# SL_FPGA_Auto_2E.net
KiCad netlist of a schematic drawn in Altium Designer
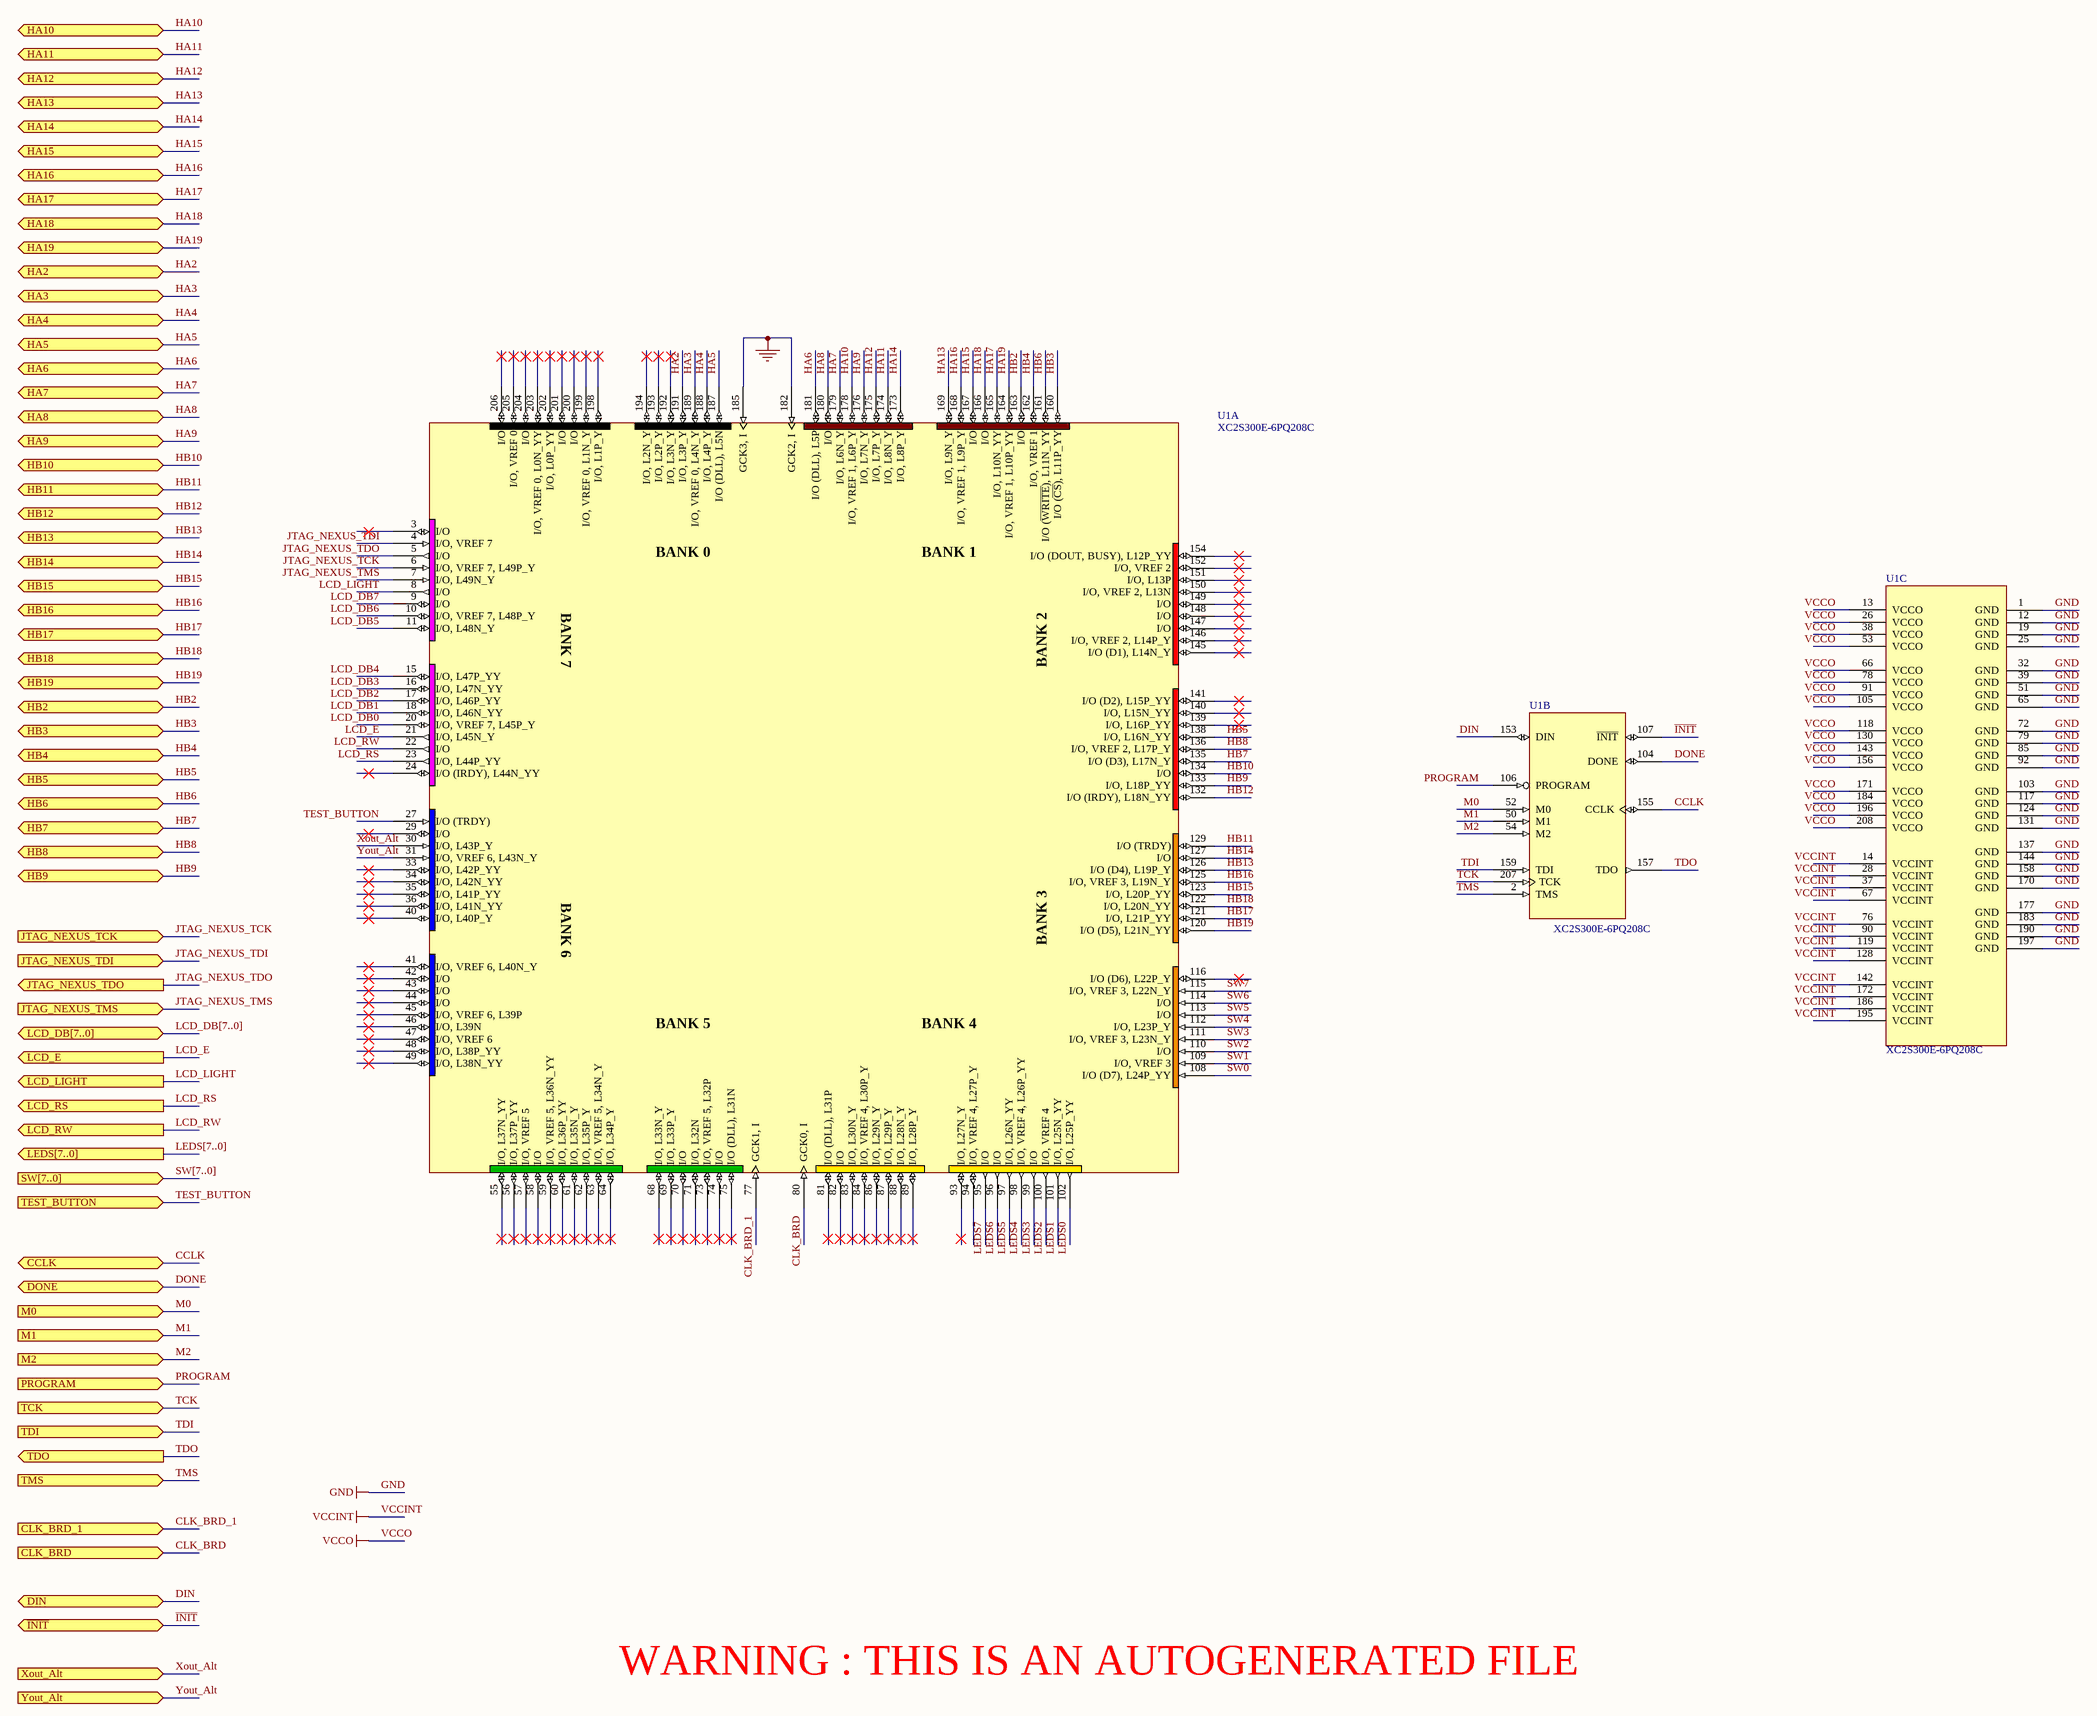
[diagram p0: SL_FPGA_Auto_2E.SchDoc]

(export (version "E")
  (design (tool "Eeschema 10.0.6"))
  (components
    (comp (ref "U1")
      (value "XC2S300E-6PQ208C")
      (footprint "PQ208")
      (description "Spartan-IIE 1.8V FPGA, 208-Pin PQFP, Standard Performance, Commercial Grade")
      (fields (field (name "PUBLISHER") "Altium Limited"))
      (libsource (lib "SpiritLevel_2E") (part "XC2S300E-6PQ208C"))
    )
  )
  (nets
    (net (code "1") (name "/CCLK") (class "Default")
      (node (ref "U1") (pin "155") (pinfunction "CCLK_155") (pintype "bidirectional"))
    )
    (net (code "2") (name "/CLK_BRD") (class "Default")
      (node (ref "U1") (pin "80") (pinfunction "GCK0,_I_80") (pintype "input"))
    )
    (net (code "3") (name "/CLK_BRD_1") (class "Default")
      (node (ref "U1") (pin "77") (pinfunction "GCK1,_I_77") (pintype "input"))
    )
    (net (code "4") (name "/DIN") (class "Default")
      (node (ref "U1") (pin "153") (pinfunction "DIN_153") (pintype "bidirectional"))
    )
    (net (code "5") (name "/DONE") (class "Default")
      (node (ref "U1") (pin "104") (pinfunction "DONE_104") (pintype "bidirectional"))
    )
    (net (code "6") (name "/HA2") (class "Default")
      (node (ref "U1") (pin "191") (pinfunction "I/O,_L3P_Y_191") (pintype "bidirectional"))
    )
    (net (code "7") (name "/HA3") (class "Default")
      (node (ref "U1") (pin "189") (pinfunction "I/O,_VREF_0,_L4N_Y_189") (pintype "bidirectional"))
    )
    (net (code "8") (name "/HA4") (class "Default")
      (node (ref "U1") (pin "188") (pinfunction "I/O,_L4P_Y_188") (pintype "bidirectional"))
    )
    (net (code "9") (name "/HA5") (class "Default")
      (node (ref "U1") (pin "187") (pinfunction "I/O_(DLL),_L5N_187") (pintype "bidirectional"))
    )
    (net (code "10") (name "/HA6") (class "Default")
      (node (ref "U1") (pin "181") (pinfunction "I/O_(DLL),_L5P_181") (pintype "bidirectional"))
    )
    (net (code "11") (name "/HA7") (class "Default")
      (node (ref "U1") (pin "179") (pinfunction "I/O,_L6N_Y_179") (pintype "bidirectional"))
    )
    (net (code "12") (name "/HA8") (class "Default")
      (node (ref "U1") (pin "180") (pinfunction "I/O_180") (pintype "bidirectional"))
    )
    (net (code "13") (name "/HA9") (class "Default")
      (node (ref "U1") (pin "176") (pinfunction "I/O,_L7N_Y_176") (pintype "bidirectional"))
    )
    (net (code "14") (name "/HA10") (class "Default")
      (node (ref "U1") (pin "178") (pinfunction "I/O,_VREF_1,_L6P_Y_178") (pintype "bidirectional"))
    )
    (net (code "15") (name "/HA11") (class "Default")
      (node (ref "U1") (pin "174") (pinfunction "I/O,_L8N_Y_174") (pintype "bidirectional"))
    )
    (net (code "16") (name "/HA12") (class "Default")
      (node (ref "U1") (pin "175") (pinfunction "I/O,_L7P_Y_175") (pintype "bidirectional"))
    )
    (net (code "17") (name "/HA13") (class "Default")
      (node (ref "U1") (pin "169") (pinfunction "I/O,_L9N_Y_169") (pintype "bidirectional"))
    )
    (net (code "18") (name "/HA14") (class "Default")
      (node (ref "U1") (pin "173") (pinfunction "I/O,_L8P_Y_173") (pintype "bidirectional"))
    )
    (net (code "19") (name "/HA15") (class "Default")
      (node (ref "U1") (pin "167") (pinfunction "I/O_167") (pintype "bidirectional"))
    )
    (net (code "20") (name "/HA16") (class "Default")
      (node (ref "U1") (pin "168") (pinfunction "I/O,_VREF_1,_L9P_Y_168") (pintype "bidirectional"))
    )
    (net (code "21") (name "/HA17") (class "Default")
      (node (ref "U1") (pin "165") (pinfunction "I/O,_L10N_YY_165") (pintype "bidirectional"))
    )
    (net (code "22") (name "/HA18") (class "Default")
      (node (ref "U1") (pin "166") (pinfunction "I/O_166") (pintype "bidirectional"))
    )
    (net (code "23") (name "/HA19") (class "Default")
      (node (ref "U1") (pin "164") (pinfunction "I/O,_VREF_1,_L10P_YY_164") (pintype "bidirectional"))
    )
    (net (code "24") (name "/HB2") (class "Default")
      (node (ref "U1") (pin "163") (pinfunction "I/O_163") (pintype "bidirectional"))
    )
    (net (code "25") (name "/HB3") (class "Default")
      (node (ref "U1") (pin "160") (pinfunction "I/O_(~{CS}),_L11P_YY_160") (pintype "bidirectional"))
    )
    (net (code "26") (name "/HB4") (class "Default")
      (node (ref "U1") (pin "162") (pinfunction "I/O,_VREF_1_162") (pintype "bidirectional"))
    )
    (net (code "27") (name "/HB5") (class "Default")
      (node (ref "U1") (pin "138") (pinfunction "I/O,_L16N_YY_138") (pintype "bidirectional"))
    )
    (net (code "28") (name "/HB6") (class "Default")
      (node (ref "U1") (pin "161") (pinfunction "I/O_(~{WRITE}),_L11N_YY_161") (pintype "bidirectional"))
    )
    (net (code "29") (name "/HB7") (class "Default")
      (node (ref "U1") (pin "135") (pinfunction "I/O_(D3),_L17N_Y_135") (pintype "bidirectional"))
    )
    (net (code "30") (name "/HB8") (class "Default")
      (node (ref "U1") (pin "136") (pinfunction "I/O,_VREF_2,_L17P_Y_136") (pintype "bidirectional"))
    )
    (net (code "31") (name "/HB9") (class "Default")
      (node (ref "U1") (pin "133") (pinfunction "I/O,_L18P_YY_133") (pintype "bidirectional"))
    )
    (net (code "32") (name "/HB10") (class "Default")
      (node (ref "U1") (pin "134") (pinfunction "I/O_134") (pintype "bidirectional"))
    )
    (net (code "33") (name "/HB11") (class "Default")
      (node (ref "U1") (pin "129") (pinfunction "I/O_(TRDY)_129") (pintype "bidirectional"))
    )
    (net (code "34") (name "/HB12") (class "Default")
      (node (ref "U1") (pin "132") (pinfunction "I/O_(IRDY),_L18N_YY_132") (pintype "bidirectional"))
    )
    (net (code "35") (name "/HB13") (class "Default")
      (node (ref "U1") (pin "126") (pinfunction "I/O_(D4),_L19P_Y_126") (pintype "bidirectional"))
    )
    (net (code "36") (name "/HB14") (class "Default")
      (node (ref "U1") (pin "127") (pinfunction "I/O_127") (pintype "bidirectional"))
    )
    (net (code "37") (name "/HB15") (class "Default")
      (node (ref "U1") (pin "123") (pinfunction "I/O,_L20P_YY_123") (pintype "bidirectional"))
    )
    (net (code "38") (name "/HB16") (class "Default")
      (node (ref "U1") (pin "125") (pinfunction "I/O,_VREF_3,_L19N_Y_125") (pintype "bidirectional"))
    )
    (net (code "39") (name "/HB17") (class "Default")
      (node (ref "U1") (pin "121") (pinfunction "I/O,_L21P_YY_121") (pintype "bidirectional"))
    )
    (net (code "40") (name "/HB18") (class "Default")
      (node (ref "U1") (pin "122") (pinfunction "I/O,_L20N_YY_122") (pintype "bidirectional"))
    )
    (net (code "41") (name "/HB19") (class "Default")
      (node (ref "U1") (pin "120") (pinfunction "I/O_(D5),_L21N_YY_120") (pintype "bidirectional"))
    )
    (net (code "42") (name "/JTAG_NEXUS_TCK") (class "Default")
      (node (ref "U1") (pin "6") (pinfunction "I/O,_VREF_7,_L49P_Y_6") (pintype "input"))
    )
    (net (code "43") (name "/JTAG_NEXUS_TDI") (class "Default")
      (node (ref "U1") (pin "4") (pinfunction "I/O,_VREF_7_4") (pintype "input"))
    )
    (net (code "44") (name "/JTAG_NEXUS_TDO") (class "Default")
      (node (ref "U1") (pin "5") (pinfunction "I/O_5") (pintype "output"))
    )
    (net (code "45") (name "/JTAG_NEXUS_TMS") (class "Default")
      (node (ref "U1") (pin "7") (pinfunction "I/O,_L49N_Y_7") (pintype "input"))
    )
    (net (code "46") (name "/LCD_DB0") (class "Default")
      (node (ref "U1") (pin "20") (pinfunction "I/O,_VREF_7,_L45P_Y_20") (pintype "bidirectional"))
    )
    (net (code "47") (name "/LCD_DB1") (class "Default")
      (node (ref "U1") (pin "18") (pinfunction "I/O,_L46N_YY_18") (pintype "bidirectional"))
    )
    (net (code "48") (name "/LCD_DB2") (class "Default")
      (node (ref "U1") (pin "17") (pinfunction "I/O,_L46P_YY_17") (pintype "bidirectional"))
    )
    (net (code "49") (name "/LCD_DB3") (class "Default")
      (node (ref "U1") (pin "16") (pinfunction "I/O,_L47N_YY_16") (pintype "bidirectional"))
    )
    (net (code "50") (name "/LCD_DB4") (class "Default")
      (node (ref "U1") (pin "15") (pinfunction "I/O,_L47P_YY_15") (pintype "bidirectional"))
    )
    (net (code "51") (name "/LCD_DB5") (class "Default")
      (node (ref "U1") (pin "11") (pinfunction "I/O,_L48N_Y_11") (pintype "bidirectional"))
    )
    (net (code "52") (name "/LCD_DB6") (class "Default")
      (node (ref "U1") (pin "10") (pinfunction "I/O,_VREF_7,_L48P_Y_10") (pintype "bidirectional"))
    )
    (net (code "53") (name "/LCD_DB7") (class "Default")
      (node (ref "U1") (pin "9") (pinfunction "I/O_9") (pintype "bidirectional"))
    )
    (net (code "55") (name "/LCD_E") (class "Default")
      (node (ref "U1") (pin "21") (pinfunction "I/O,_L45N_Y_21") (pintype "output"))
    )
    (net (code "56") (name "/LCD_LIGHT") (class "Default")
      (node (ref "U1") (pin "8") (pinfunction "I/O_8") (pintype "output"))
    )
    (net (code "57") (name "/LCD_RS") (class "Default")
      (node (ref "U1") (pin "23") (pinfunction "I/O,_L44P_YY_23") (pintype "output"))
    )
    (net (code "58") (name "/LCD_RW") (class "Default")
      (node (ref "U1") (pin "22") (pinfunction "I/O_22") (pintype "output"))
    )
    (net (code "59") (name "/LEDS0") (class "Default")
      (node (ref "U1") (pin "102") (pinfunction "I/O,_L25P_YY_102") (pintype "output"))
    )
    (net (code "60") (name "/LEDS1") (class "Default")
      (node (ref "U1") (pin "101") (pinfunction "I/O,_L25N_YY_101") (pintype "output"))
    )
    (net (code "61") (name "/LEDS2") (class "Default")
      (node (ref "U1") (pin "100") (pinfunction "I/O,_VREF_4_100") (pintype "output"))
    )
    (net (code "62") (name "/LEDS3") (class "Default")
      (node (ref "U1") (pin "99") (pinfunction "I/O_99") (pintype "output"))
    )
    (net (code "63") (name "/LEDS4") (class "Default")
      (node (ref "U1") (pin "98") (pinfunction "I/O,_VREF_4,_L26P_YY_98") (pintype "output"))
    )
    (net (code "64") (name "/LEDS5") (class "Default")
      (node (ref "U1") (pin "97") (pinfunction "I/O,_L26N_YY_97") (pintype "output"))
    )
    (net (code "65") (name "/LEDS6") (class "Default")
      (node (ref "U1") (pin "96") (pinfunction "I/O_96") (pintype "output"))
    )
    (net (code "66") (name "/LEDS7") (class "Default")
      (node (ref "U1") (pin "95") (pinfunction "I/O_95") (pintype "output"))
    )
    (net (code "68") (name "/M0") (class "Default")
      (node (ref "U1") (pin "52") (pinfunction "M0_52") (pintype "input"))
    )
    (net (code "69") (name "/M1") (class "Default")
      (node (ref "U1") (pin "50") (pinfunction "M1_50") (pintype "input"))
    )
    (net (code "70") (name "/M2") (class "Default")
      (node (ref "U1") (pin "54") (pinfunction "M2_54") (pintype "input"))
    )
    (net (code "71") (name "/PROGRAM") (class "Default")
      (node (ref "U1") (pin "106") (pinfunction "PROGRAM_106") (pintype "input"))
    )
    (net (code "72") (name "/SW0") (class "Default")
      (node (ref "U1") (pin "108") (pinfunction "I/O_(D7),_L24P_YY_108") (pintype "input"))
    )
    (net (code "73") (name "/SW1") (class "Default")
      (node (ref "U1") (pin "109") (pinfunction "I/O,_VREF_3_109") (pintype "input"))
    )
    (net (code "74") (name "/SW2") (class "Default")
      (node (ref "U1") (pin "110") (pinfunction "I/O_110") (pintype "input"))
    )
    (net (code "75") (name "/SW3") (class "Default")
      (node (ref "U1") (pin "111") (pinfunction "I/O,_VREF_3,_L23N_Y_111") (pintype "input"))
    )
    (net (code "76") (name "/SW4") (class "Default")
      (node (ref "U1") (pin "112") (pinfunction "I/O,_L23P_Y_112") (pintype "input"))
    )
    (net (code "77") (name "/SW5") (class "Default")
      (node (ref "U1") (pin "113") (pinfunction "I/O_113") (pintype "input"))
    )
    (net (code "78") (name "/SW6") (class "Default")
      (node (ref "U1") (pin "114") (pinfunction "I/O_114") (pintype "input"))
    )
    (net (code "79") (name "/SW7") (class "Default")
      (node (ref "U1") (pin "115") (pinfunction "I/O,_VREF_3,_L22N_Y_115") (pintype "input"))
    )
    (net (code "81") (name "/TCK") (class "Default")
      (node (ref "U1") (pin "207") (pinfunction "TCK_207") (pintype "input"))
    )
    (net (code "82") (name "/TDI") (class "Default")
      (node (ref "U1") (pin "159") (pinfunction "TDI_159") (pintype "input"))
    )
    (net (code "83") (name "/TDO") (class "Default")
      (node (ref "U1") (pin "157") (pinfunction "TDO_157") (pintype "output"))
    )
    (net (code "84") (name "/TEST_BUTTON") (class "Default")
      (node (ref "U1") (pin "27") (pinfunction "I/O_(TRDY)_27") (pintype "input"))
    )
    (net (code "85") (name "/TMS") (class "Default")
      (node (ref "U1") (pin "2") (pinfunction "TMS_2") (pintype "input"))
    )
    (net (code "86") (name "/Xout_Alt") (class "Default")
      (node (ref "U1") (pin "30") (pinfunction "I/O,_L43P_Y_30") (pintype "input"))
    )
    (net (code "87") (name "/Yout_Alt") (class "Default")
      (node (ref "U1") (pin "31") (pinfunction "I/O,_VREF_6,_L43N_Y_31") (pintype "input"))
    )
    (net (code "88") (name "/~{INIT}") (class "Default")
      (node (ref "U1") (pin "107") (pinfunction "~{INIT}_107") (pintype "bidirectional"))
    )
    (net (code "89") (name "GND") (class "Default")
      (node (ref "U1") (pin "1") (pinfunction "GND_1") (pintype "power_in"))
      (node (ref "U1") (pin "103") (pinfunction "GND_103") (pintype "power_in"))
      (node (ref "U1") (pin "117") (pinfunction "GND_117") (pintype "power_in"))
      (node (ref "U1") (pin "12") (pinfunction "GND_12") (pintype "power_in"))
      (node (ref "U1") (pin "124") (pinfunction "GND_124") (pintype "power_in"))
      (node (ref "U1") (pin "131") (pinfunction "GND_131") (pintype "power_in"))
      (node (ref "U1") (pin "137") (pinfunction "GND_137") (pintype "power_in"))
      (node (ref "U1") (pin "144") (pinfunction "GND_144") (pintype "power_in"))
      (node (ref "U1") (pin "158") (pinfunction "GND_158") (pintype "power_in"))
      (node (ref "U1") (pin "170") (pinfunction "GND_170") (pintype "power_in"))
      (node (ref "U1") (pin "177") (pinfunction "GND_177") (pintype "power_in"))
      (node (ref "U1") (pin "182") (pinfunction "GCK2,_I_182") (pintype "input"))
      (node (ref "U1") (pin "183") (pinfunction "GND_183") (pintype "power_in"))
      (node (ref "U1") (pin "185") (pinfunction "GCK3,_I_185") (pintype "input"))
      (node (ref "U1") (pin "19") (pinfunction "GND_19") (pintype "power_in"))
      (node (ref "U1") (pin "190") (pinfunction "GND_190") (pintype "power_in"))
      (node (ref "U1") (pin "197") (pinfunction "GND_197") (pintype "power_in"))
      (node (ref "U1") (pin "25") (pinfunction "GND_25") (pintype "power_in"))
      (node (ref "U1") (pin "32") (pinfunction "GND_32") (pintype "power_in"))
      (node (ref "U1") (pin "39") (pinfunction "GND_39") (pintype "power_in"))
      (node (ref "U1") (pin "51") (pinfunction "GND_51") (pintype "power_in"))
      (node (ref "U1") (pin "65") (pinfunction "GND_65") (pintype "power_in"))
      (node (ref "U1") (pin "72") (pinfunction "GND_72") (pintype "power_in"))
      (node (ref "U1") (pin "79") (pinfunction "GND_79") (pintype "power_in"))
      (node (ref "U1") (pin "85") (pinfunction "GND_85") (pintype "power_in"))
      (node (ref "U1") (pin "92") (pinfunction "GND_92") (pintype "power_in"))
    )
    (net (code "90") (name "VCCINT") (class "Default")
      (node (ref "U1") (pin "119") (pinfunction "VCCINT_119") (pintype "power_in"))
      (node (ref "U1") (pin "128") (pinfunction "VCCINT_128") (pintype "power_in"))
      (node (ref "U1") (pin "14") (pinfunction "VCCINT_14") (pintype "power_in"))
      (node (ref "U1") (pin "142") (pinfunction "VCCINT_142") (pintype "power_in"))
      (node (ref "U1") (pin "172") (pinfunction "VCCINT_172") (pintype "power_in"))
      (node (ref "U1") (pin "186") (pinfunction "VCCINT_186") (pintype "power_in"))
      (node (ref "U1") (pin "195") (pinfunction "VCCINT_195") (pintype "power_in"))
      (node (ref "U1") (pin "28") (pinfunction "VCCINT_28") (pintype "power_in"))
      (node (ref "U1") (pin "37") (pinfunction "VCCINT_37") (pintype "power_in"))
      (node (ref "U1") (pin "67") (pinfunction "VCCINT_67") (pintype "power_in"))
      (node (ref "U1") (pin "76") (pinfunction "VCCINT_76") (pintype "power_in"))
      (node (ref "U1") (pin "90") (pinfunction "VCCINT_90") (pintype "power_in"))
    )
    (net (code "91") (name "VCCO") (class "Default")
      (node (ref "U1") (pin "105") (pinfunction "VCCO_105") (pintype "power_in"))
      (node (ref "U1") (pin "118") (pinfunction "VCCO_118") (pintype "power_in"))
      (node (ref "U1") (pin "13") (pinfunction "VCCO_13") (pintype "power_in"))
      (node (ref "U1") (pin "130") (pinfunction "VCCO_130") (pintype "power_in"))
      (node (ref "U1") (pin "143") (pinfunction "VCCO_143") (pintype "power_in"))
      (node (ref "U1") (pin "156") (pinfunction "VCCO_156") (pintype "power_in"))
      (node (ref "U1") (pin "171") (pinfunction "VCCO_171") (pintype "power_in"))
      (node (ref "U1") (pin "184") (pinfunction "VCCO_184") (pintype "power_in"))
      (node (ref "U1") (pin "196") (pinfunction "VCCO_196") (pintype "power_in"))
      (node (ref "U1") (pin "208") (pinfunction "VCCO_208") (pintype "power_in"))
      (node (ref "U1") (pin "26") (pinfunction "VCCO_26") (pintype "power_in"))
      (node (ref "U1") (pin "38") (pinfunction "VCCO_38") (pintype "power_in"))
      (node (ref "U1") (pin "53") (pinfunction "VCCO_53") (pintype "power_in"))
      (node (ref "U1") (pin "66") (pinfunction "VCCO_66") (pintype "power_in"))
      (node (ref "U1") (pin "78") (pinfunction "VCCO_78") (pintype "power_in"))
      (node (ref "U1") (pin "91") (pinfunction "VCCO_91") (pintype "power_in"))
    )
    (net (code "92") (name "unconnected-(U1A-I{slash}O,_L0P_YY-Pad202)") (class "Default")
      (node (ref "U1") (pin "202") (pinfunction "I/O,_L0P_YY_202") (pintype "bidirectional"))
    )
    (net (code "93") (name "unconnected-(U1A-I{slash}O,_L1P_Y-Pad198)") (class "Default")
      (node (ref "U1") (pin "198") (pinfunction "I/O,_L1P_Y_198") (pintype "bidirectional"))
    )
    (net (code "94") (name "unconnected-(U1A-I{slash}O,_L2N_Y-Pad194)") (class "Default")
      (node (ref "U1") (pin "194") (pinfunction "I/O,_L2N_Y_194") (pintype "bidirectional"))
    )
    (net (code "95") (name "unconnected-(U1A-I{slash}O,_L2P_Y-Pad193)") (class "Default")
      (node (ref "U1") (pin "193") (pinfunction "I/O,_L2P_Y_193") (pintype "bidirectional"))
    )
    (net (code "96") (name "unconnected-(U1A-I{slash}O,_L3N_Y-Pad192)") (class "Default")
      (node (ref "U1") (pin "192") (pinfunction "I/O,_L3N_Y_192") (pintype "bidirectional"))
    )
    (net (code "97") (name "unconnected-(U1A-I{slash}O,_L13P-Pad151)") (class "Default")
      (node (ref "U1") (pin "151") (pinfunction "I/O,_L13P_151") (pintype "bidirectional"))
    )
    (net (code "98") (name "unconnected-(U1A-I{slash}O,_L15N_YY-Pad140)") (class "Default")
      (node (ref "U1") (pin "140") (pinfunction "I/O,_L15N_YY_140") (pintype "bidirectional"))
    )
    (net (code "99") (name "unconnected-(U1A-I{slash}O,_L16P_YY-Pad139)") (class "Default")
      (node (ref "U1") (pin "139") (pinfunction "I/O,_L16P_YY_139") (pintype "bidirectional"))
    )
    (net (code "100") (name "unconnected-(U1A-I{slash}O,_L27N_Y-Pad93)") (class "Default")
      (node (ref "U1") (pin "93") (pinfunction "I/O,_L27N_Y_93") (pintype "bidirectional"))
    )
    (net (code "101") (name "unconnected-(U1A-I{slash}O,_L28N_Y-Pad88)") (class "Default")
      (node (ref "U1") (pin "88") (pinfunction "I/O,_L28N_Y_88") (pintype "bidirectional"))
    )
    (net (code "102") (name "unconnected-(U1A-I{slash}O,_L28P_Y-Pad89)") (class "Default")
      (node (ref "U1") (pin "89") (pinfunction "I/O,_L28P_Y_89") (pintype "bidirectional"))
    )
    (net (code "103") (name "unconnected-(U1A-I{slash}O,_L29N_Y-Pad86)") (class "Default")
      (node (ref "U1") (pin "86") (pinfunction "I/O,_L29N_Y_86") (pintype "bidirectional"))
    )
    (net (code "104") (name "unconnected-(U1A-I{slash}O,_L29P_Y-Pad87)") (class "Default")
      (node (ref "U1") (pin "87") (pinfunction "I/O,_L29P_Y_87") (pintype "bidirectional"))
    )
    (net (code "105") (name "unconnected-(U1A-I{slash}O,_L30N_Y-Pad83)") (class "Default")
      (node (ref "U1") (pin "83") (pinfunction "I/O,_L30N_Y_83") (pintype "bidirectional"))
    )
    (net (code "106") (name "unconnected-(U1A-I{slash}O,_L32N-Pad71)") (class "Default")
      (node (ref "U1") (pin "71") (pinfunction "I/O,_L32N_71") (pintype "bidirectional"))
    )
    (net (code "107") (name "unconnected-(U1A-I{slash}O,_L33N_Y-Pad68)") (class "Default")
      (node (ref "U1") (pin "68") (pinfunction "I/O,_L33N_Y_68") (pintype "bidirectional"))
    )
    (net (code "108") (name "unconnected-(U1A-I{slash}O,_L33P_Y-Pad69)") (class "Default")
      (node (ref "U1") (pin "69") (pinfunction "I/O,_L33P_Y_69") (pintype "bidirectional"))
    )
    (net (code "109") (name "unconnected-(U1A-I{slash}O,_L34P_Y-Pad64)") (class "Default")
      (node (ref "U1") (pin "64") (pinfunction "I/O,_L34P_Y_64") (pintype "bidirectional"))
    )
    (net (code "110") (name "unconnected-(U1A-I{slash}O,_L35N_Y-Pad61)") (class "Default")
      (node (ref "U1") (pin "61") (pinfunction "I/O,_L35N_Y_61") (pintype "bidirectional"))
    )
    (net (code "111") (name "unconnected-(U1A-I{slash}O,_L35P_Y-Pad62)") (class "Default")
      (node (ref "U1") (pin "62") (pinfunction "I/O,_L35P_Y_62") (pintype "bidirectional"))
    )
    (net (code "112") (name "unconnected-(U1A-I{slash}O,_L36P_YY-Pad60)") (class "Default")
      (node (ref "U1") (pin "60") (pinfunction "I/O,_L36P_YY_60") (pintype "bidirectional"))
    )
    (net (code "113") (name "unconnected-(U1A-I{slash}O,_L37N_YY-Pad55)") (class "Default")
      (node (ref "U1") (pin "55") (pinfunction "I/O,_L37N_YY_55") (pintype "bidirectional"))
    )
    (net (code "114") (name "unconnected-(U1A-I{slash}O,_L37P_YY-Pad56)") (class "Default")
      (node (ref "U1") (pin "56") (pinfunction "I/O,_L37P_YY_56") (pintype "bidirectional"))
    )
    (net (code "115") (name "unconnected-(U1A-I{slash}O,_L38N_YY-Pad49)") (class "Default")
      (node (ref "U1") (pin "49") (pinfunction "I/O,_L38N_YY_49") (pintype "bidirectional"))
    )
    (net (code "116") (name "unconnected-(U1A-I{slash}O,_L38P_YY-Pad48)") (class "Default")
      (node (ref "U1") (pin "48") (pinfunction "I/O,_L38P_YY_48") (pintype "bidirectional"))
    )
    (net (code "117") (name "unconnected-(U1A-I{slash}O,_L39N-Pad46)") (class "Default")
      (node (ref "U1") (pin "46") (pinfunction "I/O,_L39N_46") (pintype "bidirectional"))
    )
    (net (code "118") (name "unconnected-(U1A-I{slash}O,_L40P_Y-Pad40)") (class "Default")
      (node (ref "U1") (pin "40") (pinfunction "I/O,_L40P_Y_40") (pintype "bidirectional"))
    )
    (net (code "119") (name "unconnected-(U1A-I{slash}O,_L41N_YY-Pad36)") (class "Default")
      (node (ref "U1") (pin "36") (pinfunction "I/O,_L41N_YY_36") (pintype "bidirectional"))
    )
    (net (code "120") (name "unconnected-(U1A-I{slash}O,_L41P_YY-Pad35)") (class "Default")
      (node (ref "U1") (pin "35") (pinfunction "I/O,_L41P_YY_35") (pintype "bidirectional"))
    )
    (net (code "121") (name "unconnected-(U1A-I{slash}O,_L42N_YY-Pad34)") (class "Default")
      (node (ref "U1") (pin "34") (pinfunction "I/O,_L42N_YY_34") (pintype "bidirectional"))
    )
    (net (code "122") (name "unconnected-(U1A-I{slash}O,_L42P_YY-Pad33)") (class "Default")
      (node (ref "U1") (pin "33") (pinfunction "I/O,_L42P_YY_33") (pintype "bidirectional"))
    )
    (net (code "123") (name "unconnected-(U1A-I{slash}O,_VREF_0,_L0N_YY-Pad203)") (class "Default")
      (node (ref "U1") (pin "203") (pinfunction "I/O,_VREF_0,_L0N_YY_203") (pintype "bidirectional"))
    )
    (net (code "124") (name "unconnected-(U1A-I{slash}O,_VREF_0,_L1N_Y-Pad199)") (class "Default")
      (node (ref "U1") (pin "199") (pinfunction "I/O,_VREF_0,_L1N_Y_199") (pintype "bidirectional"))
    )
    (net (code "125") (name "unconnected-(U1A-I{slash}O,_VREF_0-Pad205)") (class "Default")
      (node (ref "U1") (pin "205") (pinfunction "I/O,_VREF_0_205") (pintype "bidirectional"))
    )
    (net (code "126") (name "unconnected-(U1A-I{slash}O,_VREF_2,_L13N-Pad150)") (class "Default")
      (node (ref "U1") (pin "150") (pinfunction "I/O,_VREF_2,_L13N_150") (pintype "bidirectional"))
    )
    (net (code "127") (name "unconnected-(U1A-I{slash}O,_VREF_2,_L14P_Y-Pad146)") (class "Default")
      (node (ref "U1") (pin "146") (pinfunction "I/O,_VREF_2,_L14P_Y_146") (pintype "bidirectional"))
    )
    (net (code "128") (name "unconnected-(U1A-I{slash}O,_VREF_2-Pad152)") (class "Default")
      (node (ref "U1") (pin "152") (pinfunction "I/O,_VREF_2_152") (pintype "bidirectional"))
    )
    (net (code "129") (name "unconnected-(U1A-I{slash}O,_VREF_4,_L27P_Y-Pad94)") (class "Default")
      (node (ref "U1") (pin "94") (pinfunction "I/O,_VREF_4,_L27P_Y_94") (pintype "bidirectional"))
    )
    (net (code "130") (name "unconnected-(U1A-I{slash}O,_VREF_4,_L30P_Y-Pad84)") (class "Default")
      (node (ref "U1") (pin "84") (pinfunction "I/O,_VREF_4,_L30P_Y_84") (pintype "bidirectional"))
    )
    (net (code "131") (name "unconnected-(U1A-I{slash}O,_VREF_5,_L32P-Pad73)") (class "Default")
      (node (ref "U1") (pin "73") (pinfunction "I/O,_VREF_5,_L32P_73") (pintype "bidirectional"))
    )
    (net (code "132") (name "unconnected-(U1A-I{slash}O,_VREF_5,_L34N_Y-Pad63)") (class "Default")
      (node (ref "U1") (pin "63") (pinfunction "I/O,_VREF_5,_L34N_Y_63") (pintype "bidirectional"))
    )
    (net (code "133") (name "unconnected-(U1A-I{slash}O,_VREF_5,_L36N_YY-Pad59)") (class "Default")
      (node (ref "U1") (pin "59") (pinfunction "I/O,_VREF_5,_L36N_YY_59") (pintype "bidirectional"))
    )
    (net (code "134") (name "unconnected-(U1A-I{slash}O,_VREF_5-Pad57)") (class "Default")
      (node (ref "U1") (pin "57") (pinfunction "I/O,_VREF_5_57") (pintype "bidirectional"))
    )
    (net (code "135") (name "unconnected-(U1A-I{slash}O,_VREF_6,_L39P-Pad45)") (class "Default")
      (node (ref "U1") (pin "45") (pinfunction "I/O,_VREF_6,_L39P_45") (pintype "bidirectional"))
    )
    (net (code "136") (name "unconnected-(U1A-I{slash}O,_VREF_6,_L40N_Y-Pad41)") (class "Default")
      (node (ref "U1") (pin "41") (pinfunction "I/O,_VREF_6,_L40N_Y_41") (pintype "bidirectional"))
    )
    (net (code "137") (name "unconnected-(U1A-I{slash}O,_VREF_6-Pad47)") (class "Default")
      (node (ref "U1") (pin "47") (pinfunction "I/O,_VREF_6_47") (pintype "bidirectional"))
    )
    (net (code "138") (name "unconnected-(U1A-I{slash}O-Pad3)") (class "Default")
      (node (ref "U1") (pin "3") (pinfunction "I/O_3") (pintype "bidirectional"))
    )
    (net (code "139") (name "unconnected-(U1A-I{slash}O-Pad29)") (class "Default")
      (node (ref "U1") (pin "29") (pinfunction "I/O_29") (pintype "bidirectional"))
    )
    (net (code "140") (name "unconnected-(U1A-I{slash}O-Pad42)") (class "Default")
      (node (ref "U1") (pin "42") (pinfunction "I/O_42") (pintype "bidirectional"))
    )
    (net (code "141") (name "unconnected-(U1A-I{slash}O-Pad43)") (class "Default")
      (node (ref "U1") (pin "43") (pinfunction "I/O_43") (pintype "bidirectional"))
    )
    (net (code "142") (name "unconnected-(U1A-I{slash}O-Pad44)") (class "Default")
      (node (ref "U1") (pin "44") (pinfunction "I/O_44") (pintype "bidirectional"))
    )
    (net (code "143") (name "unconnected-(U1A-I{slash}O-Pad58)") (class "Default")
      (node (ref "U1") (pin "58") (pinfunction "I/O_58") (pintype "bidirectional"))
    )
    (net (code "144") (name "unconnected-(U1A-I{slash}O-Pad70)") (class "Default")
      (node (ref "U1") (pin "70") (pinfunction "I/O_70") (pintype "bidirectional"))
    )
    (net (code "145") (name "unconnected-(U1A-I{slash}O-Pad74)") (class "Default")
      (node (ref "U1") (pin "74") (pinfunction "I/O_74") (pintype "bidirectional"))
    )
    (net (code "146") (name "unconnected-(U1A-I{slash}O-Pad82)") (class "Default")
      (node (ref "U1") (pin "82") (pinfunction "I/O_82") (pintype "bidirectional"))
    )
    (net (code "147") (name "unconnected-(U1A-I{slash}O-Pad147)") (class "Default")
      (node (ref "U1") (pin "147") (pinfunction "I/O_147") (pintype "bidirectional"))
    )
    (net (code "148") (name "unconnected-(U1A-I{slash}O-Pad148)") (class "Default")
      (node (ref "U1") (pin "148") (pinfunction "I/O_148") (pintype "bidirectional"))
    )
    (net (code "149") (name "unconnected-(U1A-I{slash}O-Pad149)") (class "Default")
      (node (ref "U1") (pin "149") (pinfunction "I/O_149") (pintype "bidirectional"))
    )
    (net (code "150") (name "unconnected-(U1A-I{slash}O-Pad200)") (class "Default")
      (node (ref "U1") (pin "200") (pinfunction "I/O_200") (pintype "bidirectional"))
    )
    (net (code "151") (name "unconnected-(U1A-I{slash}O-Pad201)") (class "Default")
      (node (ref "U1") (pin "201") (pinfunction "I/O_201") (pintype "bidirectional"))
    )
    (net (code "152") (name "unconnected-(U1A-I{slash}O-Pad204)") (class "Default")
      (node (ref "U1") (pin "204") (pinfunction "I/O_204") (pintype "bidirectional"))
    )
    (net (code "153") (name "unconnected-(U1A-I{slash}O-Pad206)") (class "Default")
      (node (ref "U1") (pin "206") (pinfunction "I/O_206") (pintype "bidirectional"))
    )
    (net (code "154") (name "unconnected-(U1A-I{slash}O_(D1),_L14N_Y-Pad145)") (class "Default")
      (node (ref "U1") (pin "145") (pinfunction "I/O_(D1),_L14N_Y_145") (pintype "bidirectional"))
    )
    (net (code "155") (name "unconnected-(U1A-I{slash}O_(D2),_L15P_YY-Pad141)") (class "Default")
      (node (ref "U1") (pin "141") (pinfunction "I/O_(D2),_L15P_YY_141") (pintype "bidirectional"))
    )
    (net (code "156") (name "unconnected-(U1A-I{slash}O_(D6),_L22P_Y-Pad116)") (class "Default")
      (node (ref "U1") (pin "116") (pinfunction "I/O_(D6),_L22P_Y_116") (pintype "bidirectional"))
    )
    (net (code "157") (name "unconnected-(U1A-I{slash}O_(DLL),_L31N-Pad75)") (class "Default")
      (node (ref "U1") (pin "75") (pinfunction "I/O_(DLL),_L31N_75") (pintype "bidirectional"))
    )
    (net (code "158") (name "unconnected-(U1A-I{slash}O_(DLL),_L31P-Pad81)") (class "Default")
      (node (ref "U1") (pin "81") (pinfunction "I/O_(DLL),_L31P_81") (pintype "bidirectional"))
    )
    (net (code "159") (name "unconnected-(U1A-I{slash}O_(DOUT,_BUSY),_L12P_YY-Pad154)") (class "Default")
      (node (ref "U1") (pin "154") (pinfunction "I/O_(DOUT,_BUSY),_L12P_YY_154") (pintype "bidirectional"))
    )
    (net (code "160") (name "unconnected-(U1A-I{slash}O_(IRDY),_L44N_YY-Pad24)") (class "Default")
      (node (ref "U1") (pin "24") (pinfunction "I/O_(IRDY),_L44N_YY_24") (pintype "bidirectional"))
    )
  )
)
